# PowanPowan.net
KiCad netlist of a schematic drawn in EAGLE
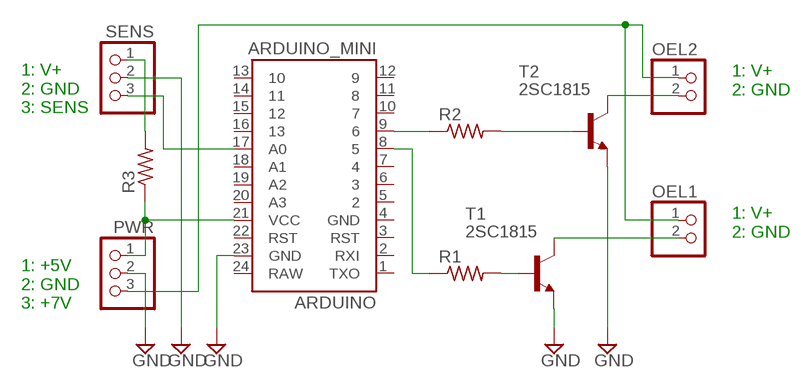
[diagram p0: schematic, sheet 1]

(export (version "E")
  (design (tool "Eeschema 10.0.6"))
  (components
    (comp (ref "ARDUINO")
      (value "ARDUINO_MINI")
      (footprint "eagle-import:ARDUINO_MINI")
      (libsource (lib "eagle-import") (part "ARDUINO_MINI"))
    )
    (comp (ref "OEL1")
      (value "PINHD-1X2")
      (footprint "eagle-import:1X02")
      (libsource (lib "eagle-import") (part "PINHD-1X2"))
    )
    (comp (ref "OEL2")
      (value "PINHD-1X2")
      (footprint "eagle-import:1X02")
      (libsource (lib "eagle-import") (part "PINHD-1X2"))
    )
    (comp (ref "PWR")
      (value "PINHD-1X3")
      (footprint "eagle-import:1X03")
      (libsource (lib "eagle-import") (part "PINHD-1X3"))
    )
    (comp (ref "R1")
      (value "R-US_0204/7")
      (footprint "eagle-import:0204_7")
      (libsource (lib "eagle-import") (part "R-US_0204/7"))
    )
    (comp (ref "R2")
      (value "R-US_0204/7")
      (footprint "eagle-import:0204_7")
      (libsource (lib "eagle-import") (part "R-US_0204/7"))
    )
    (comp (ref "R3")
      (value "R-US_0204/7")
      (footprint "eagle-import:0204_7")
      (libsource (lib "eagle-import") (part "R-US_0204/7"))
    )
    (comp (ref "SENS")
      (value "PINHD-1X3")
      (footprint "eagle-import:1X03")
      (libsource (lib "eagle-import") (part "PINHD-1X3"))
    )
    (comp (ref "T1")
      (value "2SC1815")
      (footprint "eagle-import:TO92-ECB")
      (libsource (lib "eagle-import") (part "2SC1815"))
    )
    (comp (ref "T2")
      (value "2SC1815")
      (footprint "eagle-import:TO92-ECB")
      (libsource (lib "eagle-import") (part "2SC1815"))
    )
  )
  (nets
    (net (code "1") (name "GND") (class "Default")
      (node (ref "ARDUINO") (pin "23") (pinfunction "GND_23") (pintype "bidirectional"))
      (node (ref "PWR") (pin "2") (pinfunction "2_2") (pintype "passive"))
      (node (ref "SENS") (pin "2") (pinfunction "2_2") (pintype "passive"))
      (node (ref "T1") (pin "E") (pinfunction "E_E") (pintype "passive"))
      (node (ref "T2") (pin "E") (pinfunction "E_E") (pintype "passive"))
    )
    (net (code "2") (name "Net-(ARDUINO-5)") (class "Default")
      (node (ref "ARDUINO") (pin "8") (pinfunction "5_8") (pintype "bidirectional"))
      (node (ref "R1") (pin "1") (pinfunction "1_1") (pintype "passive"))
    )
    (net (code "3") (name "Net-(ARDUINO-6)") (class "Default")
      (node (ref "ARDUINO") (pin "9") (pinfunction "6_9") (pintype "bidirectional"))
      (node (ref "R2") (pin "1") (pinfunction "1_1") (pintype "passive"))
    )
    (net (code "4") (name "Net-(ARDUINO-A0)") (class "Default")
      (node (ref "ARDUINO") (pin "17") (pinfunction "A0_17") (pintype "bidirectional"))
      (node (ref "SENS") (pin "3") (pinfunction "3_3") (pintype "passive"))
    )
    (net (code "5") (name "Net-(ARDUINO-VCC)") (class "Default")
      (node (ref "ARDUINO") (pin "21") (pinfunction "VCC_21") (pintype "bidirectional"))
      (node (ref "PWR") (pin "1") (pinfunction "1_1") (pintype "passive"))
      (node (ref "R3") (pin "1") (pinfunction "1_1") (pintype "passive"))
    )
    (net (code "6") (name "Net-(OEL1-Pad1)") (class "Default")
      (node (ref "OEL1") (pin "1") (pinfunction "1_1") (pintype "passive"))
      (node (ref "OEL2") (pin "1") (pinfunction "1_1") (pintype "passive"))
      (node (ref "PWR") (pin "3") (pinfunction "3_3") (pintype "passive"))
    )
    (net (code "7") (name "Net-(OEL1-Pad2)") (class "Default")
      (node (ref "OEL1") (pin "2") (pinfunction "2_2") (pintype "passive"))
      (node (ref "T1") (pin "C") (pinfunction "C_C") (pintype "passive"))
    )
    (net (code "8") (name "Net-(OEL2-Pad2)") (class "Default")
      (node (ref "OEL2") (pin "2") (pinfunction "2_2") (pintype "passive"))
      (node (ref "T2") (pin "C") (pinfunction "C_C") (pintype "passive"))
    )
    (net (code "9") (name "Net-(R1-Pad2)") (class "Default")
      (node (ref "R1") (pin "2") (pinfunction "2_2") (pintype "passive"))
      (node (ref "T1") (pin "B") (pinfunction "B_B") (pintype "passive"))
    )
    (net (code "10") (name "Net-(R2-Pad2)") (class "Default")
      (node (ref "R2") (pin "2") (pinfunction "2_2") (pintype "passive"))
      (node (ref "T2") (pin "B") (pinfunction "B_B") (pintype "passive"))
    )
    (net (code "11") (name "Net-(R3-Pad2)") (class "Default")
      (node (ref "R3") (pin "2") (pinfunction "2_2") (pintype "passive"))
      (node (ref "SENS") (pin "1") (pinfunction "1_1") (pintype "passive"))
    )
    (net (code "12") (name "unconnected-(ARDUINO-2-Pad5)") (class "Default")
      (node (ref "ARDUINO") (pin "5") (pinfunction "2_5") (pintype "bidirectional"))
    )
    (net (code "13") (name "unconnected-(ARDUINO-3-Pad6)") (class "Default")
      (node (ref "ARDUINO") (pin "6") (pinfunction "3_6") (pintype "bidirectional"))
    )
    (net (code "14") (name "unconnected-(ARDUINO-4-Pad7)") (class "Default")
      (node (ref "ARDUINO") (pin "7") (pinfunction "4_7") (pintype "bidirectional"))
    )
    (net (code "15") (name "unconnected-(ARDUINO-7-Pad10)") (class "Default")
      (node (ref "ARDUINO") (pin "10") (pinfunction "7_10") (pintype "bidirectional"))
    )
    (net (code "16") (name "unconnected-(ARDUINO-8-Pad11)") (class "Default")
      (node (ref "ARDUINO") (pin "11") (pinfunction "8_11") (pintype "bidirectional"))
    )
    (net (code "17") (name "unconnected-(ARDUINO-9-Pad12)") (class "Default")
      (node (ref "ARDUINO") (pin "12") (pinfunction "9_12") (pintype "bidirectional"))
    )
    (net (code "18") (name "unconnected-(ARDUINO-10-Pad13)") (class "Default")
      (node (ref "ARDUINO") (pin "13") (pinfunction "10_13") (pintype "bidirectional"))
    )
    (net (code "19") (name "unconnected-(ARDUINO-11-Pad14)") (class "Default")
      (node (ref "ARDUINO") (pin "14") (pinfunction "11_14") (pintype "bidirectional"))
    )
    (net (code "20") (name "unconnected-(ARDUINO-12-Pad15)") (class "Default")
      (node (ref "ARDUINO") (pin "15") (pinfunction "12_15") (pintype "bidirectional"))
    )
    (net (code "21") (name "unconnected-(ARDUINO-13-Pad16)") (class "Default")
      (node (ref "ARDUINO") (pin "16") (pinfunction "13_16") (pintype "bidirectional"))
    )
    (net (code "22") (name "unconnected-(ARDUINO-A1-Pad18)") (class "Default")
      (node (ref "ARDUINO") (pin "18") (pinfunction "A1_18") (pintype "bidirectional"))
    )
    (net (code "23") (name "unconnected-(ARDUINO-A2-Pad19)") (class "Default")
      (node (ref "ARDUINO") (pin "19") (pinfunction "A2_19") (pintype "bidirectional"))
    )
    (net (code "24") (name "unconnected-(ARDUINO-A3-Pad20)") (class "Default")
      (node (ref "ARDUINO") (pin "20") (pinfunction "A3_20") (pintype "bidirectional"))
    )
    (net (code "25") (name "unconnected-(ARDUINO-GND-Pad4)") (class "Default")
      (node (ref "ARDUINO") (pin "4") (pinfunction "GND_4") (pintype "bidirectional"))
    )
    (net (code "26") (name "unconnected-(ARDUINO-RAW-Pad24)") (class "Default")
      (node (ref "ARDUINO") (pin "24") (pinfunction "RAW_24") (pintype "bidirectional"))
    )
    (net (code "27") (name "unconnected-(ARDUINO-RST-Pad3)") (class "Default")
      (node (ref "ARDUINO") (pin "3") (pinfunction "RST_3") (pintype "bidirectional"))
    )
    (net (code "28") (name "unconnected-(ARDUINO-RST-Pad22)") (class "Default")
      (node (ref "ARDUINO") (pin "22") (pinfunction "RST_22") (pintype "bidirectional"))
    )
    (net (code "29") (name "unconnected-(ARDUINO-RXI-Pad2)") (class "Default")
      (node (ref "ARDUINO") (pin "2") (pinfunction "RXI_2") (pintype "bidirectional"))
    )
    (net (code "30") (name "unconnected-(ARDUINO-TXO-Pad1)") (class "Default")
      (node (ref "ARDUINO") (pin "1") (pinfunction "TXO_1") (pintype "bidirectional"))
    )
  )
)
